# hex_inverter.net
KiCad netlist of a schematic drawn in Altium Designer
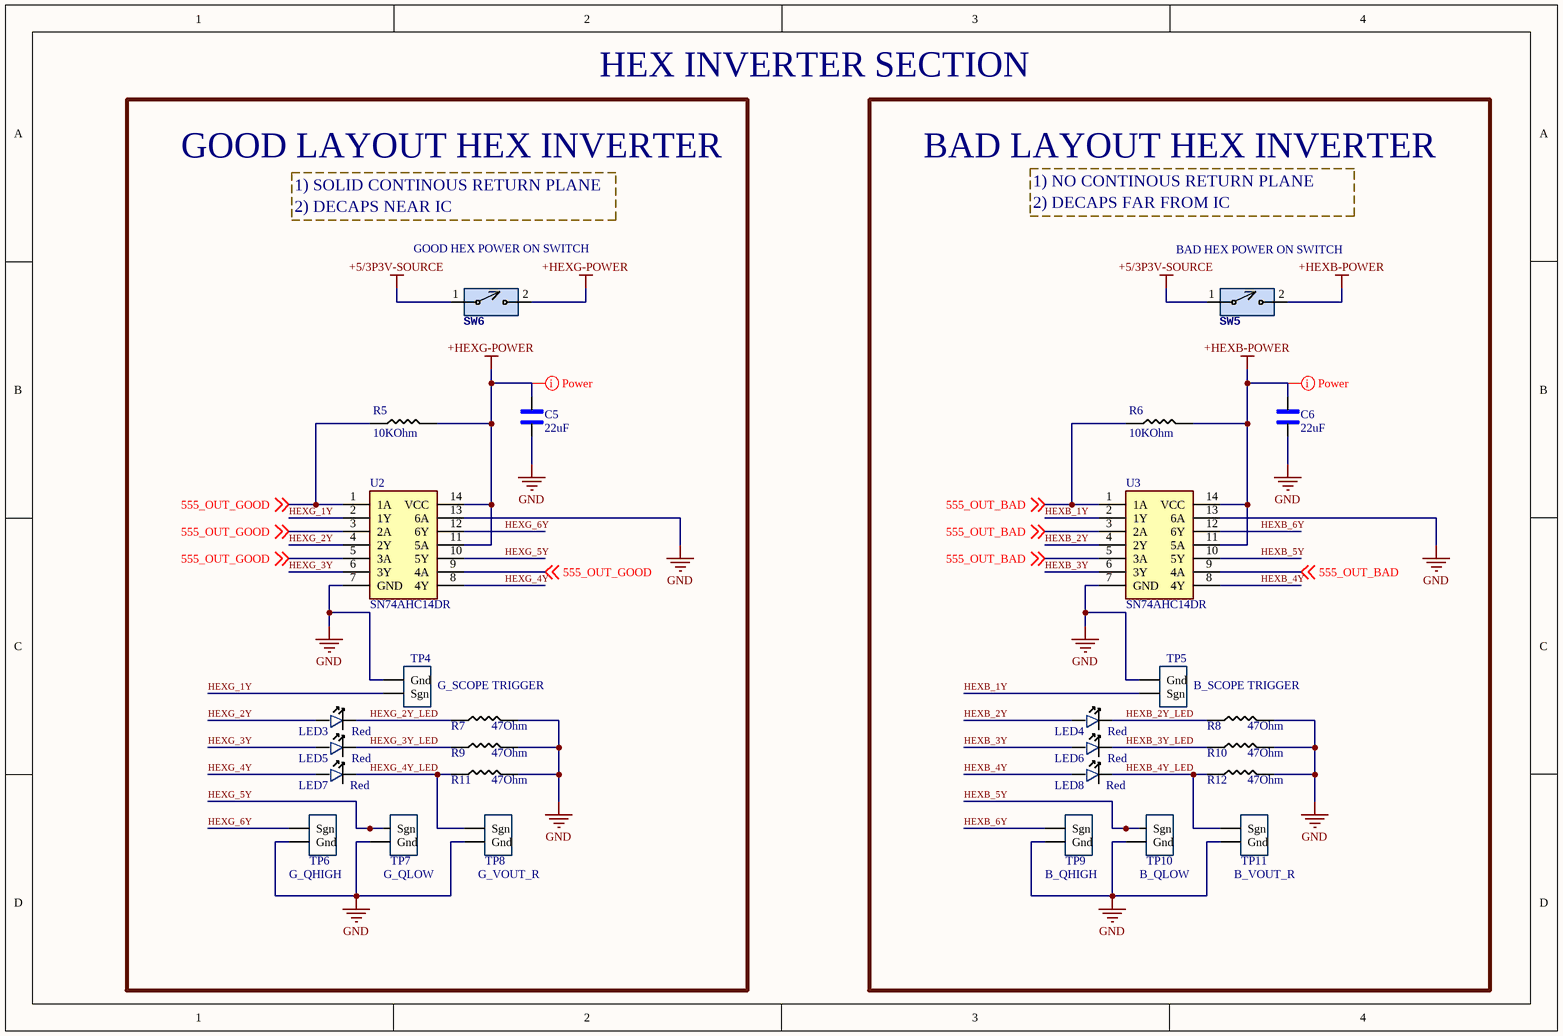
[diagram p0: hex_inverter.SchDoc]

(export (version "E")
  (design (tool "Eeschema 10.0.6"))
  (components
    (comp (ref "C5")
      (value "22uF")
      (footprint "1206_Passive_Capacitor")
      (description "22uF ±10% 25V X5R 1206 Multilayer Ceramic Capacitors MLCC - SMD/SMT RoHS")
      (fields (field (name "MFR PART #") "CL31A226KAHNNNE") (field (name "LCSC PART#") "C12891"))
      (libsource (lib "ECEN5730Lib_2023_05_DS (1)") (part "C_22uF_1206"))
    )
    (comp (ref "C6")
      (value "22uF")
      (footprint "1206_Passive_Capacitor")
      (description "22uF ±10% 25V X5R 1206 Multilayer Ceramic Capacitors MLCC - SMD/SMT RoHS")
      (fields (field (name "MFR PART #") "CL31A226KAHNNNE") (field (name "LCSC PART#") "C12891"))
      (libsource (lib "ECEN5730Lib_2023_05_DS (1)") (part "C_22uF_1206"))
    )
    (comp (ref "LED3")
      (value "Red")
      (footprint "LED_1206")
      (description "Red 621~631nm 1206 Light Emitting Diodes (LED) RoHS")
      (fields (field (name "MFR PART #") "15-21/R6C-FQ1R1B/2T") (field (name "LCSC PART#") "C93133"))
      (libsource (lib "ECEN5730Lib_2023_05_DS (1)") (part "LED_RED_1206"))
    )
    (comp (ref "LED4")
      (value "Red")
      (footprint "LED_1206")
      (description "Red 621~631nm 1206 Light Emitting Diodes (LED) RoHS")
      (fields (field (name "MFR PART #") "15-21/R6C-FQ1R1B/2T") (field (name "LCSC PART#") "C93133"))
      (libsource (lib "ECEN5730Lib_2023_05_DS (1)") (part "LED_RED_1206"))
    )
    (comp (ref "LED5")
      (value "Red")
      (footprint "LED_1206")
      (description "Red 621~631nm 1206 Light Emitting Diodes (LED) RoHS")
      (fields (field (name "MFR PART #") "15-21/R6C-FQ1R1B/2T") (field (name "LCSC PART#") "C93133"))
      (libsource (lib "ECEN5730Lib_2023_05_DS (1)") (part "LED_RED_1206"))
    )
    (comp (ref "LED6")
      (value "Red")
      (footprint "LED_1206")
      (description "Red 621~631nm 1206 Light Emitting Diodes (LED) RoHS")
      (fields (field (name "MFR PART #") "15-21/R6C-FQ1R1B/2T") (field (name "LCSC PART#") "C93133"))
      (libsource (lib "ECEN5730Lib_2023_05_DS (1)") (part "LED_RED_1206"))
    )
    (comp (ref "LED7")
      (value "Red")
      (footprint "LED_1206")
      (description "Red 621~631nm 1206 Light Emitting Diodes (LED) RoHS")
      (fields (field (name "MFR PART #") "15-21/R6C-FQ1R1B/2T") (field (name "LCSC PART#") "C93133"))
      (libsource (lib "ECEN5730Lib_2023_05_DS (1)") (part "LED_RED_1206"))
    )
    (comp (ref "LED8")
      (value "Red")
      (footprint "LED_1206")
      (description "Red 621~631nm 1206 Light Emitting Diodes (LED) RoHS")
      (fields (field (name "MFR PART #") "15-21/R6C-FQ1R1B/2T") (field (name "LCSC PART#") "C93133"))
      (libsource (lib "ECEN5730Lib_2023_05_DS (1)") (part "LED_RED_1206"))
    )
    (comp (ref "R5")
      (value "10KOhm")
      (footprint "1206_Passive_Resitor")
      (description "10 kOhms ±5% 0.25W, 1/4W Chip Resistor 1206 (3216 Metric) Automotive AEC-Q200 Thick Film")
      (fields (field (name "MFR PART #") "RMCF1206FT10K0") (field (name "LCSC PART#") "C17902"))
      (libsource (lib "ECEN5730Lib_2023_05_DS (1)") (part "R_10KOhm_1206"))
    )
    (comp (ref "R6")
      (value "10KOhm")
      (footprint "1206_Passive_Resitor")
      (description "10 kOhms ±5% 0.25W, 1/4W Chip Resistor 1206 (3216 Metric) Automotive AEC-Q200 Thick Film")
      (fields (field (name "MFR PART #") "RMCF1206FT10K0") (field (name "LCSC PART#") "C17902"))
      (libsource (lib "ECEN5730Lib_2023_05_DS (1)") (part "R_10KOhm_1206"))
    )
    (comp (ref "R7")
      (value "47Ohm")
      (footprint "1206_Passive_Resitor")
      (description "47Ω ±5% 0.25W ±200ppm/℃ 1206 Chip Resistor - Surface Mount RoHS")
      (fields (field (name "MFR PART #") "1206W4J0470T5E") (field (name "LCSC PART#") "C25384"))
      (libsource (lib "ECEN5730Lib_2023_05_DS (1)") (part "R_47Ohm_1206"))
    )
    (comp (ref "R8")
      (value "47Ohm")
      (footprint "1206_Passive_Resitor")
      (description "47Ω ±5% 0.25W ±200ppm/℃ 1206 Chip Resistor - Surface Mount RoHS")
      (fields (field (name "MFR PART #") "1206W4J0470T5E") (field (name "LCSC PART#") "C25384"))
      (libsource (lib "ECEN5730Lib_2023_05_DS (1)") (part "R_47Ohm_1206"))
    )
    (comp (ref "R9")
      (value "47Ohm")
      (footprint "1206_Passive_Resitor")
      (description "47Ω ±5% 0.25W ±200ppm/℃ 1206 Chip Resistor - Surface Mount RoHS")
      (fields (field (name "MFR PART #") "1206W4J0470T5E") (field (name "LCSC PART#") "C25384"))
      (libsource (lib "ECEN5730Lib_2023_05_DS (1)") (part "R_47Ohm_1206"))
    )
    (comp (ref "R10")
      (value "47Ohm")
      (footprint "1206_Passive_Resitor")
      (description "47Ω ±5% 0.25W ±200ppm/℃ 1206 Chip Resistor - Surface Mount RoHS")
      (fields (field (name "MFR PART #") "1206W4J0470T5E") (field (name "LCSC PART#") "C25384"))
      (libsource (lib "ECEN5730Lib_2023_05_DS (1)") (part "R_47Ohm_1206"))
    )
    (comp (ref "R11")
      (value "47Ohm")
      (footprint "1206_Passive_Resitor")
      (description "47Ω ±5% 0.25W ±200ppm/℃ 1206 Chip Resistor - Surface Mount RoHS")
      (fields (field (name "MFR PART #") "1206W4J0470T5E") (field (name "LCSC PART#") "C25384"))
      (libsource (lib "ECEN5730Lib_2023_05_DS (1)") (part "R_47Ohm_1206"))
    )
    (comp (ref "R12")
      (value "47Ohm")
      (footprint "1206_Passive_Resitor")
      (description "47Ω ±5% 0.25W ±200ppm/℃ 1206 Chip Resistor - Surface Mount RoHS")
      (fields (field (name "MFR PART #") "1206W4J0470T5E") (field (name "LCSC PART#") "C25384"))
      (libsource (lib "ECEN5730Lib_2023_05_DS (1)") (part "R_47Ohm_1206"))
    )
    (comp (ref "SW5")
      (value "SW_2Pin_100mil_Switch")
      (footprint "2Pin-Header-Conn")
      (description "2Pin Header")
      (fields (field (name "LCSC PART#") "C124375"))
      (libsource (lib "ECEN5730Lib_2023_05_DS (1)") (part "SW_2Pin_100mil_Switch"))
    )
    (comp (ref "SW6")
      (value "SW_2Pin_100mil_Switch")
      (footprint "2Pin-Header-Conn")
      (description "2Pin Header")
      (fields (field (name "LCSC PART#") "C124375"))
      (libsource (lib "ECEN5730Lib_2023_05_DS (1)") (part "SW_2Pin_100mil_Switch"))
    )
    (comp (ref "TP4")
      (value "10x Probe TP")
      (footprint "TP10x_Probe")
      (description "Test Point 300 mil centers")
      (libsource (lib "") (part "TP_10x_Probe_1"))
    )
    (comp (ref "TP5")
      (value "10x Probe TP")
      (footprint "TP10x_Probe")
      (description "Test Point 300 mil centers")
      (libsource (lib "") (part "TP_10x_Probe_1"))
    )
    (comp (ref "TP6")
      (value "10x Probe TP")
      (footprint "TP10x_Probe")
      (description "Test Point 300 mil centers")
      (libsource (lib "ECEN5730Lib_2023_05_DS (1)") (part "TP_10x_Probe"))
    )
    (comp (ref "TP7")
      (value "10x Probe TP")
      (footprint "TP10x_Probe")
      (description "Test Point 300 mil centers")
      (libsource (lib "ECEN5730Lib_2023_05_DS (1)") (part "TP_10x_Probe"))
    )
    (comp (ref "TP8")
      (value "10x Probe TP")
      (footprint "TP10x_Probe")
      (description "Test Point 300 mil centers")
      (libsource (lib "ECEN5730Lib_2023_05_DS (1)") (part "TP_10x_Probe"))
    )
    (comp (ref "TP9")
      (value "10x Probe TP")
      (footprint "TP10x_Probe")
      (description "Test Point 300 mil centers")
      (libsource (lib "ECEN5730Lib_2023_05_DS (1)") (part "TP_10x_Probe"))
    )
    (comp (ref "TP10")
      (value "10x Probe TP")
      (footprint "TP10x_Probe")
      (description "Test Point 300 mil centers")
      (libsource (lib "ECEN5730Lib_2023_05_DS (1)") (part "TP_10x_Probe"))
    )
    (comp (ref "TP11")
      (value "10x Probe TP")
      (footprint "TP10x_Probe")
      (description "Test Point 300 mil centers")
      (libsource (lib "ECEN5730Lib_2023_05_DS (1)") (part "TP_10x_Probe"))
    )
    (comp (ref "U2")
      (value "SN74AHC14DR")
      (footprint "HEX_74AC14")
      (description "Inverter IC 6 Channel Schmitt Trigger 14-SOIC")
      (fields (field (name "LCSC PART#") "C6942"))
      (libsource (lib "ECEN5730Lib_2023_05_DS (1)") (part "U_74AHC14"))
    )
    (comp (ref "U3")
      (value "SN74AHC14DR")
      (footprint "HEX_74AC14")
      (description "Inverter IC 6 Channel Schmitt Trigger 14-SOIC")
      (fields (field (name "LCSC PART#") "C6942"))
      (libsource (lib "ECEN5730Lib_2023_05_DS (1)") (part "U_74AHC14"))
    )
  )
  (nets
    (net (code "1") (name "+5{slash}3P3V-SOURCE") (class "Default")
      (node (ref "SW5") (pin "1") (pinfunction "1_1") (pintype "passive"))
      (node (ref "SW6") (pin "1") (pinfunction "1_1") (pintype "passive"))
    )
    (net (code "2") (name "+HEXB-POWER") (class "Default")
      (node (ref "C6") (pin "2") (pinfunction "2_2") (pintype "passive"))
      (node (ref "R6") (pin "2") (pinfunction "2_2") (pintype "passive"))
      (node (ref "SW5") (pin "2") (pinfunction "2_2") (pintype "passive"))
      (node (ref "U3") (pin "11") (pinfunction "5A_11") (pintype "passive"))
      (node (ref "U3") (pin "14") (pinfunction "VCC_14") (pintype "passive"))
    )
    (net (code "3") (name "+HEXG-POWER") (class "Default")
      (node (ref "C5") (pin "2") (pinfunction "2_2") (pintype "passive"))
      (node (ref "R5") (pin "2") (pinfunction "2_2") (pintype "passive"))
      (node (ref "SW6") (pin "2") (pinfunction "2_2") (pintype "passive"))
      (node (ref "U2") (pin "11") (pinfunction "5A_11") (pintype "passive"))
      (node (ref "U2") (pin "14") (pinfunction "VCC_14") (pintype "passive"))
    )
    (net (code "4") (name "/HEXB_1Y") (class "Default")
      (node (ref "TP5") (pin "1") (pinfunction "Sgn_1") (pintype "passive"))
      (node (ref "U3") (pin "2") (pinfunction "1Y_2") (pintype "passive"))
    )
    (net (code "5") (name "/HEXB_2Y") (class "Default")
      (node (ref "LED4") (pin "1") (pinfunction "1_1") (pintype "passive"))
      (node (ref "U3") (pin "4") (pinfunction "2Y_4") (pintype "passive"))
    )
    (net (code "6") (name "/HEXB_2Y_LED") (class "Default")
      (node (ref "LED4") (pin "2") (pinfunction "2_2") (pintype "passive"))
      (node (ref "R8") (pin "1") (pinfunction "1_1") (pintype "passive"))
    )
    (net (code "7") (name "/HEXB_3Y") (class "Default")
      (node (ref "LED6") (pin "1") (pinfunction "1_1") (pintype "passive"))
      (node (ref "U3") (pin "6") (pinfunction "3Y_6") (pintype "passive"))
    )
    (net (code "8") (name "/HEXB_3Y_LED") (class "Default")
      (node (ref "LED6") (pin "2") (pinfunction "2_2") (pintype "passive"))
      (node (ref "R10") (pin "1") (pinfunction "1_1") (pintype "passive"))
    )
    (net (code "9") (name "/HEXB_4Y") (class "Default")
      (node (ref "LED8") (pin "1") (pinfunction "1_1") (pintype "passive"))
      (node (ref "U3") (pin "8") (pinfunction "4Y_8") (pintype "passive"))
    )
    (net (code "10") (name "/HEXB_4Y_LED") (class "Default")
      (node (ref "LED8") (pin "2") (pinfunction "2_2") (pintype "passive"))
      (node (ref "R12") (pin "1") (pinfunction "1_1") (pintype "passive"))
      (node (ref "TP11") (pin "1") (pinfunction "Sgn_1") (pintype "passive"))
    )
    (net (code "11") (name "/HEXB_5Y") (class "Default")
      (node (ref "TP10") (pin "1") (pinfunction "Sgn_1") (pintype "passive"))
      (node (ref "U3") (pin "10") (pinfunction "5Y_10") (pintype "passive"))
    )
    (net (code "12") (name "/HEXB_6Y") (class "Default")
      (node (ref "TP9") (pin "1") (pinfunction "Sgn_1") (pintype "passive"))
      (node (ref "U3") (pin "12") (pinfunction "6Y_12") (pintype "passive"))
    )
    (net (code "13") (name "/HEXG_1Y") (class "Default")
      (node (ref "TP4") (pin "1") (pinfunction "Sgn_1") (pintype "passive"))
      (node (ref "U2") (pin "2") (pinfunction "1Y_2") (pintype "passive"))
    )
    (net (code "14") (name "/HEXG_2Y") (class "Default")
      (node (ref "LED3") (pin "1") (pinfunction "1_1") (pintype "passive"))
      (node (ref "U2") (pin "4") (pinfunction "2Y_4") (pintype "passive"))
    )
    (net (code "15") (name "/HEXG_2Y_LED") (class "Default")
      (node (ref "LED3") (pin "2") (pinfunction "2_2") (pintype "passive"))
      (node (ref "R7") (pin "1") (pinfunction "1_1") (pintype "passive"))
    )
    (net (code "16") (name "/HEXG_3Y") (class "Default")
      (node (ref "LED5") (pin "1") (pinfunction "1_1") (pintype "passive"))
      (node (ref "U2") (pin "6") (pinfunction "3Y_6") (pintype "passive"))
    )
    (net (code "17") (name "/HEXG_3Y_LED") (class "Default")
      (node (ref "LED5") (pin "2") (pinfunction "2_2") (pintype "passive"))
      (node (ref "R9") (pin "1") (pinfunction "1_1") (pintype "passive"))
    )
    (net (code "18") (name "/HEXG_4Y") (class "Default")
      (node (ref "LED7") (pin "1") (pinfunction "1_1") (pintype "passive"))
      (node (ref "U2") (pin "8") (pinfunction "4Y_8") (pintype "passive"))
    )
    (net (code "19") (name "/HEXG_4Y_LED") (class "Default")
      (node (ref "LED7") (pin "2") (pinfunction "2_2") (pintype "passive"))
      (node (ref "R11") (pin "1") (pinfunction "1_1") (pintype "passive"))
      (node (ref "TP8") (pin "1") (pinfunction "Sgn_1") (pintype "passive"))
    )
    (net (code "20") (name "/HEXG_5Y") (class "Default")
      (node (ref "TP7") (pin "1") (pinfunction "Sgn_1") (pintype "passive"))
      (node (ref "U2") (pin "10") (pinfunction "5Y_10") (pintype "passive"))
    )
    (net (code "21") (name "/HEXG_6Y") (class "Default")
      (node (ref "TP6") (pin "1") (pinfunction "Sgn_1") (pintype "passive"))
      (node (ref "U2") (pin "12") (pinfunction "6Y_12") (pintype "passive"))
    )
    (net (code "22") (name "555_OUT_BAD") (class "Default")
      (node (ref "R6") (pin "1") (pinfunction "1_1") (pintype "passive"))
      (node (ref "U3") (pin "1") (pinfunction "1A_1") (pintype "passive"))
      (node (ref "U3") (pin "3") (pinfunction "2A_3") (pintype "passive"))
      (node (ref "U3") (pin "5") (pinfunction "3A_5") (pintype "passive"))
      (node (ref "U3") (pin "9") (pinfunction "4A_9") (pintype "passive"))
    )
    (net (code "23") (name "555_OUT_GOOD") (class "Default")
      (node (ref "R5") (pin "1") (pinfunction "1_1") (pintype "passive"))
      (node (ref "U2") (pin "1") (pinfunction "1A_1") (pintype "passive"))
      (node (ref "U2") (pin "3") (pinfunction "2A_3") (pintype "passive"))
      (node (ref "U2") (pin "5") (pinfunction "3A_5") (pintype "passive"))
      (node (ref "U2") (pin "9") (pinfunction "4A_9") (pintype "passive"))
    )
    (net (code "24") (name "GND") (class "Default")
      (node (ref "C5") (pin "1") (pinfunction "1_1") (pintype "passive"))
      (node (ref "C6") (pin "1") (pinfunction "1_1") (pintype "passive"))
      (node (ref "R10") (pin "2") (pinfunction "2_2") (pintype "passive"))
      (node (ref "R11") (pin "2") (pinfunction "2_2") (pintype "passive"))
      (node (ref "R12") (pin "2") (pinfunction "2_2") (pintype "passive"))
      (node (ref "R7") (pin "2") (pinfunction "2_2") (pintype "passive"))
      (node (ref "R8") (pin "2") (pinfunction "2_2") (pintype "passive"))
      (node (ref "R9") (pin "2") (pinfunction "2_2") (pintype "passive"))
      (node (ref "TP10") (pin "2") (pinfunction "Gnd_2") (pintype "passive"))
      (node (ref "TP11") (pin "2") (pinfunction "Gnd_2") (pintype "passive"))
      (node (ref "TP4") (pin "2") (pinfunction "Gnd_2") (pintype "passive"))
      (node (ref "TP5") (pin "2") (pinfunction "Gnd_2") (pintype "passive"))
      (node (ref "TP6") (pin "2") (pinfunction "Gnd_2") (pintype "passive"))
      (node (ref "TP7") (pin "2") (pinfunction "Gnd_2") (pintype "passive"))
      (node (ref "TP8") (pin "2") (pinfunction "Gnd_2") (pintype "passive"))
      (node (ref "TP9") (pin "2") (pinfunction "Gnd_2") (pintype "passive"))
      (node (ref "U2") (pin "13") (pinfunction "6A_13") (pintype "passive"))
      (node (ref "U2") (pin "7") (pinfunction "GND_7") (pintype "passive"))
      (node (ref "U3") (pin "13") (pinfunction "6A_13") (pintype "passive"))
      (node (ref "U3") (pin "7") (pinfunction "GND_7") (pintype "passive"))
    )
  )
)
